# SmartCanBus.net
KiCad netlist of a schematic drawn in Altium Designer
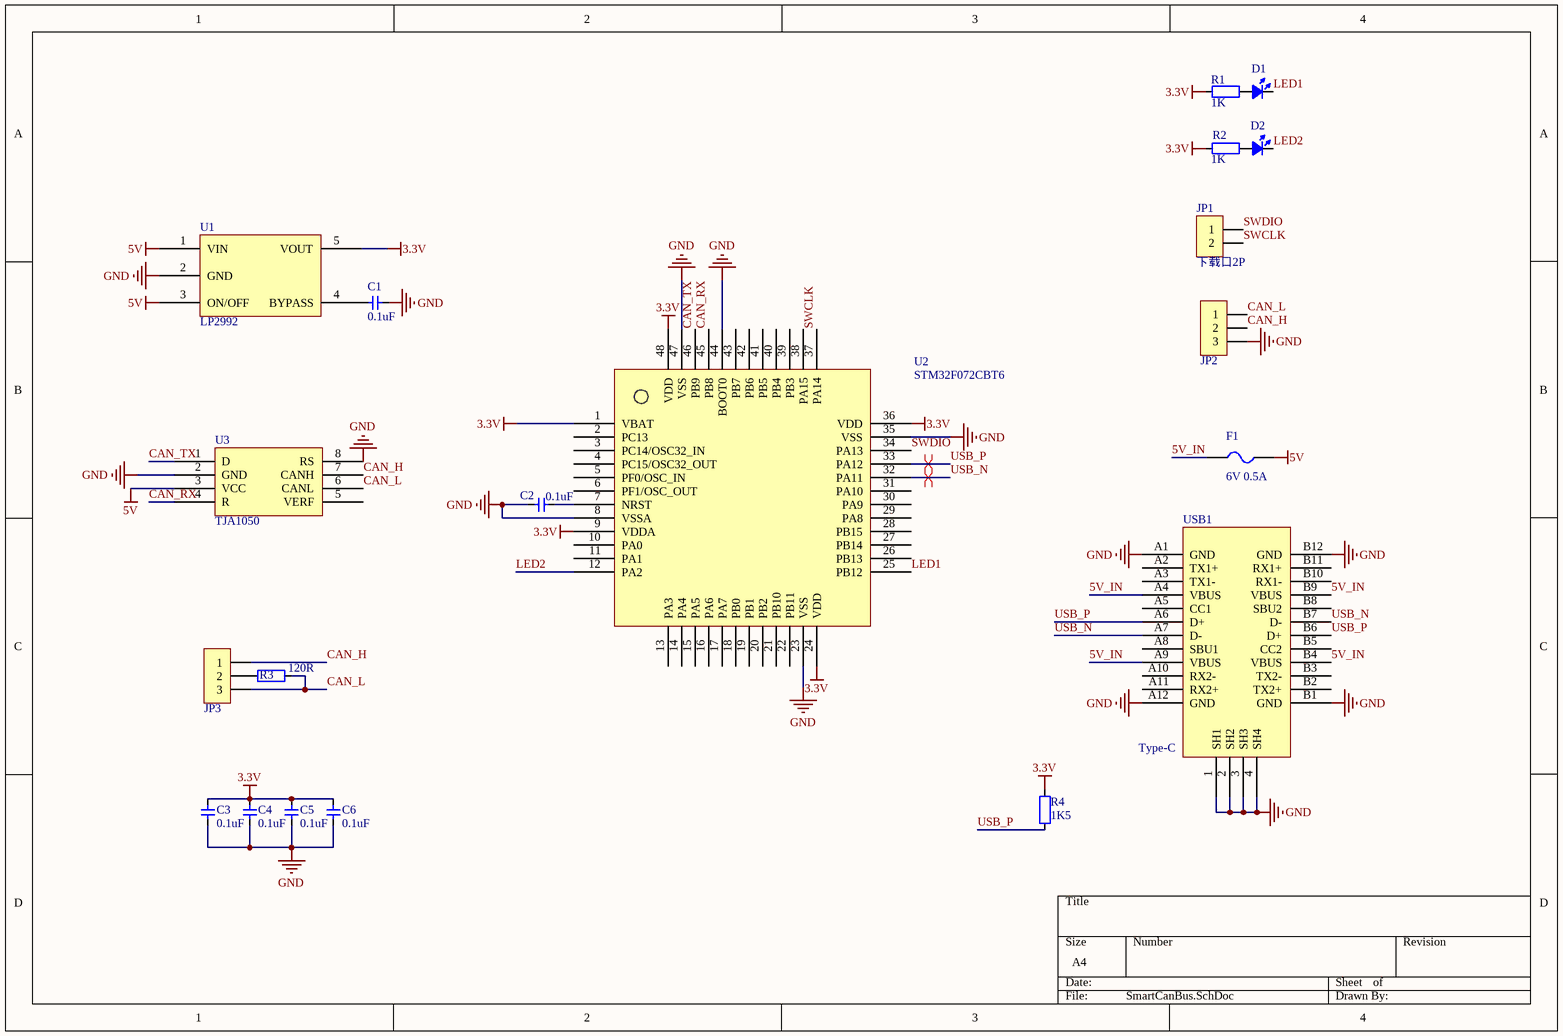
[diagram p0: SmartCanBus.SchDoc]

(export (version "E")
  (design (tool "Eeschema 10.0.6"))
  (components
    (comp (ref "C1")
      (value "0.1uF")
      (footprint "1.00-YltsPcbLib:0603_CAP")
      (description "电容")
      (libsource (lib "0.0 - YltsSchlib") (part "电容-0603"))
    )
    (comp (ref "C2")
      (value "0.1uF")
      (footprint "1.00-YltsPcbLib:0603_CAP")
      (description "电容")
      (libsource (lib "0.0 - YltsSchlib") (part "电容-0603"))
    )
    (comp (ref "C3")
      (value "0.1uF")
      (footprint "1.00-YltsPcbLib:0603_CAP")
      (description "电容")
      (libsource (lib "0.0 - YltsSchlib") (part "电容-0603"))
    )
    (comp (ref "C4")
      (value "0.1uF")
      (footprint "1.00-YltsPcbLib:0603_CAP")
      (description "电容")
      (libsource (lib "0.0 - YltsSchlib") (part "电容-0603"))
    )
    (comp (ref "C5")
      (value "0.1uF")
      (footprint "1.00-YltsPcbLib:0603_CAP")
      (description "电容")
      (libsource (lib "0.0 - YltsSchlib") (part "电容-0603"))
    )
    (comp (ref "C6")
      (value "0.1uF")
      (footprint "1.00-YltsPcbLib:0603_CAP")
      (description "电容")
      (libsource (lib "0.0 - YltsSchlib") (part "电容-0603"))
    )
    (comp (ref "D1")
      (value "LED-0603")
      (footprint "1.00-YltsPcbLib:0603_LED_RED")
      (description "发光二极管")
      (libsource (lib "0.0 - YltsSchlib") (part "二极管-0603-RED"))
    )
    (comp (ref "D2")
      (value "LED-0603")
      (footprint "1.00-YltsPcbLib:0603_LED_BLUE")
      (description "发光二极管")
      (libsource (lib "0.0 - YltsSchlib") (part "二极管-0603-BLUE"))
    )
    (comp (ref "F1")
      (value "6V 0.5A")
      (footprint "FU 0805")
      (description "贴片保险丝")
      (fields (field (name "版权归属") "封装库来自淘宝卖家 ID：黄晶宝石"))
      (libsource (lib "2.0 - 保险丝-晶振-光耦") (part "FU"))
    )
    (comp (ref "JP1")
      (value "下载口2P")
      (footprint "下载口2P")
      (description "下载口2P SWD")
      (libsource (lib "0.0 - YltsSchlib") (part "接插件-下载口2P"))
    )
    (comp (ref "JP2")
      (value "HDR-1X3")
      (footprint "KF128-3.81-3P")
      (description "3P接插件")
      (fields (field (name "版权归属") "封装库来自淘宝 ID：黄晶宝石"))
      (libsource (lib "5.5 - 接插件-脚距3.81 (150mil) ") (part "Header 3"))
    )
    (comp (ref "JP3")
      (value "HDR-1X3")
      (footprint "HDR2.54-LI-3P")
      (description "3P接插件")
      (fields (field (name "版权归属") "封装库来自淘宝 ID：黄晶宝石"))
      (libsource (lib "5.3 - 接插件-脚距2.54 (100mil) ") (part "Header 3"))
    )
    (comp (ref "R1")
      (value "1K")
      (footprint "1.00-YltsPcbLib:0603_RES")
      (description "电阻")
      (libsource (lib "") (part "电阻-0603_1"))
    )
    (comp (ref "R2")
      (value "1K")
      (footprint "1.00-YltsPcbLib:0603_RES")
      (description "电阻")
      (libsource (lib "") (part "电阻-0603_1"))
    )
    (comp (ref "R3")
      (value "120R")
      (footprint "1.00-YltsPcbLib:0603_RES")
      (description "电阻")
      (fields (field (name "Comment") "1K"))
      (libsource (lib "") (part "电阻-0603_1"))
    )
    (comp (ref "R4")
      (value "1K5")
      (footprint "1.00-YltsPcbLib:0603_RES")
      (description "电阻")
      (libsource (lib "0.0 - YltsSchlib") (part "电阻-0603"))
    )
    (comp (ref "U1")
      (value "LP2992")
      (footprint "SOT23-5N")
      (description "电源芯片")
      (libsource (lib "MySchlib") (part "LP2992"))
    )
    (comp (ref "U2")
      (value "STM32F072CBT6")
      (footprint "LQFP-48")
      (description "48MHZ Crotex-M0 32位单片机 LQFP-48_7x7x05P")
      (libsource (lib "0.0 - YltsSchlib") (part "STM32F072CBT6"))
    )
    (comp (ref "U3")
      (value "TJA1050")
      (footprint "SOIC-8 - duplicate")
      (description "CAN芯片")
      (libsource (lib "0.0 - YltsSchlib") (part "TJA1050"))
    )
    (comp (ref "USB1")
      (value "Type-C")
      (footprint "Type-C-TOP")
      (libsource (lib "0.0 - YltsSchlib") (part "接插件-USB-Type-C"))
    )
  )
  (nets
    (net (code "1") (name "/5V_IN") (class "Default")
      (node (ref "F1") (pin "1") (pinfunction "1_1") (pintype "passive"))
      (node (ref "USB1") (pin "A4") (pinfunction "VBUS_A4") (pintype "passive"))
      (node (ref "USB1") (pin "A9") (pinfunction "VBUS_A9") (pintype "passive"))
      (node (ref "USB1") (pin "B4") (pinfunction "VBUS_B4") (pintype "passive"))
      (node (ref "USB1") (pin "B9") (pinfunction "VBUS_B9") (pintype "passive"))
    )
    (net (code "2") (name "/CAN_H") (class "Default")
      (node (ref "JP2") (pin "2") (pinfunction "2_2") (pintype "passive"))
      (node (ref "JP3") (pin "1") (pinfunction "1_1") (pintype "passive"))
      (node (ref "U3") (pin "7") (pinfunction "CANH_7") (pintype "passive"))
    )
    (net (code "3") (name "/CAN_L") (class "Default")
      (node (ref "JP2") (pin "1") (pinfunction "1_1") (pintype "passive"))
      (node (ref "JP3") (pin "3") (pinfunction "3_3") (pintype "passive"))
      (node (ref "R3") (pin "2") (pinfunction "2_2") (pintype "passive"))
      (node (ref "U3") (pin "6") (pinfunction "CANL_6") (pintype "passive"))
    )
    (net (code "4") (name "/CAN_RX") (class "Default")
      (node (ref "U2") (pin "45") (pinfunction "PB8_45") (pintype "passive"))
      (node (ref "U3") (pin "4") (pinfunction "R_4") (pintype "passive"))
    )
    (net (code "5") (name "/CAN_TX") (class "Default")
      (node (ref "U2") (pin "46") (pinfunction "PB9_46") (pintype "passive"))
      (node (ref "U3") (pin "1") (pinfunction "D_1") (pintype "passive"))
    )
    (net (code "6") (name "/LED1") (class "Default")
      (node (ref "D1") (pin "2") (pinfunction "K_2") (pintype "passive"))
      (node (ref "U2") (pin "25") (pinfunction "PB12_25") (pintype "passive"))
    )
    (net (code "7") (name "/LED2") (class "Default")
      (node (ref "D2") (pin "2") (pinfunction "K_2") (pintype "passive"))
      (node (ref "U2") (pin "12") (pinfunction "PA2_12") (pintype "passive"))
    )
    (net (code "8") (name "/SWCLK") (class "Default")
      (node (ref "JP1") (pin "2") (pinfunction "2_2") (pintype "passive"))
      (node (ref "U2") (pin "37") (pinfunction "PA14_37") (pintype "passive"))
    )
    (net (code "9") (name "/SWDIO") (class "Default")
      (node (ref "JP1") (pin "1") (pinfunction "1_1") (pintype "passive"))
      (node (ref "U2") (pin "34") (pinfunction "PA13_34") (pintype "passive"))
    )
    (net (code "10") (name "/USB_N") (class "Default")
      (node (ref "U2") (pin "32") (pinfunction "PA11_32") (pintype "passive"))
      (node (ref "USB1") (pin "A7") (pinfunction "D-_A7") (pintype "passive"))
      (node (ref "USB1") (pin "B7") (pinfunction "D-_B7") (pintype "passive"))
    )
    (net (code "11") (name "/USB_P") (class "Default")
      (node (ref "R4") (pin "1") (pinfunction "1_1") (pintype "passive"))
      (node (ref "U2") (pin "33") (pinfunction "PA12_33") (pintype "passive"))
      (node (ref "USB1") (pin "A6") (pinfunction "D+_A6") (pintype "passive"))
      (node (ref "USB1") (pin "B6") (pinfunction "D+_B6") (pintype "passive"))
    )
    (net (code "12") (name "3.3V") (class "Default")
      (node (ref "C3") (pin "1") (pinfunction "1_1") (pintype "passive"))
      (node (ref "C4") (pin "1") (pinfunction "1_1") (pintype "passive"))
      (node (ref "C5") (pin "1") (pinfunction "1_1") (pintype "passive"))
      (node (ref "C6") (pin "1") (pinfunction "1_1") (pintype "passive"))
      (node (ref "R1") (pin "1") (pinfunction "1_1") (pintype "passive"))
      (node (ref "R2") (pin "1") (pinfunction "1_1") (pintype "passive"))
      (node (ref "R4") (pin "2") (pinfunction "2_2") (pintype "passive"))
      (node (ref "U1") (pin "5") (pinfunction "VOUT_5") (pintype "passive"))
      (node (ref "U2") (pin "1") (pinfunction "VBAT_1") (pintype "passive"))
      (node (ref "U2") (pin "24") (pinfunction "VDD_24") (pintype "passive"))
      (node (ref "U2") (pin "36") (pinfunction "VDD_36") (pintype "passive"))
      (node (ref "U2") (pin "48") (pinfunction "VDD_48") (pintype "passive"))
      (node (ref "U2") (pin "9") (pinfunction "VDDA_9") (pintype "passive"))
    )
    (net (code "13") (name "5V") (class "Default")
      (node (ref "F1") (pin "2") (pinfunction "2_2") (pintype "passive"))
      (node (ref "U1") (pin "1") (pinfunction "VIN_1") (pintype "passive"))
      (node (ref "U1") (pin "3") (pinfunction "ON/OFF_3") (pintype "passive"))
      (node (ref "U3") (pin "3") (pinfunction "VCC_3") (pintype "passive"))
    )
    (net (code "14") (name "GND") (class "Default")
      (node (ref "C1") (pin "1") (pinfunction "1_1") (pintype "passive"))
      (node (ref "C2") (pin "1") (pinfunction "1_1") (pintype "passive"))
      (node (ref "C3") (pin "2") (pinfunction "2_2") (pintype "passive"))
      (node (ref "C4") (pin "2") (pinfunction "2_2") (pintype "passive"))
      (node (ref "C5") (pin "2") (pinfunction "2_2") (pintype "passive"))
      (node (ref "C6") (pin "2") (pinfunction "2_2") (pintype "passive"))
      (node (ref "JP2") (pin "3") (pinfunction "3_3") (pintype "passive"))
      (node (ref "U1") (pin "2") (pinfunction "GND_2") (pintype "passive"))
      (node (ref "U2") (pin "23") (pinfunction "VSS_23") (pintype "passive"))
      (node (ref "U2") (pin "35") (pinfunction "VSS_35") (pintype "passive"))
      (node (ref "U2") (pin "44") (pinfunction "BOOT0_44") (pintype "passive"))
      (node (ref "U2") (pin "47") (pinfunction "VSS_47") (pintype "passive"))
      (node (ref "U2") (pin "8") (pinfunction "VSSA_8") (pintype "passive"))
      (node (ref "U3") (pin "2") (pinfunction "GND_2") (pintype "passive"))
      (node (ref "U3") (pin "8") (pinfunction "RS_8") (pintype "passive"))
      (node (ref "USB1") (pin "1") (pinfunction "SH1_1") (pintype "passive"))
      (node (ref "USB1") (pin "2") (pinfunction "SH2_2") (pintype "passive"))
      (node (ref "USB1") (pin "3") (pinfunction "SH3_3") (pintype "passive"))
      (node (ref "USB1") (pin "4") (pinfunction "SH4_4") (pintype "passive"))
      (node (ref "USB1") (pin "A1") (pinfunction "GND_A1") (pintype "passive"))
      (node (ref "USB1") (pin "A12") (pinfunction "GND_A12") (pintype "passive"))
      (node (ref "USB1") (pin "B1") (pinfunction "GND_B1") (pintype "passive"))
      (node (ref "USB1") (pin "B12") (pinfunction "GND_B12") (pintype "passive"))
    )
    (net (code "15") (name "Net-(D1-A)") (class "Default")
      (node (ref "D1") (pin "1") (pinfunction "A_1") (pintype "passive"))
      (node (ref "R1") (pin "2") (pinfunction "2_2") (pintype "passive"))
    )
    (net (code "16") (name "Net-(D2-A)") (class "Default")
      (node (ref "D2") (pin "1") (pinfunction "A_1") (pintype "passive"))
      (node (ref "R2") (pin "2") (pinfunction "2_2") (pintype "passive"))
    )
    (net (code "17") (name "Net-(JP3-Pad2)") (class "Default")
      (node (ref "JP3") (pin "2") (pinfunction "2_2") (pintype "passive"))
      (node (ref "R3") (pin "1") (pinfunction "1_1") (pintype "passive"))
    )
    (net (code "18") (name "Net-(U1-BYPASS)") (class "Default")
      (node (ref "C1") (pin "2") (pinfunction "2_2") (pintype "passive"))
      (node (ref "U1") (pin "4") (pinfunction "BYPASS_4") (pintype "passive"))
    )
    (net (code "19") (name "Net-(U2-NRST)") (class "Default")
      (node (ref "C2") (pin "2") (pinfunction "2_2") (pintype "passive"))
      (node (ref "U2") (pin "7") (pinfunction "NRST_7") (pintype "passive"))
    )
    (net (code "20") (name "unconnected-(U2-PA0-Pad10)") (class "Default")
      (node (ref "U2") (pin "10") (pinfunction "PA0_10") (pintype "passive"))
    )
    (net (code "21") (name "unconnected-(U2-PA1-Pad11)") (class "Default")
      (node (ref "U2") (pin "11") (pinfunction "PA1_11") (pintype "passive"))
    )
    (net (code "22") (name "unconnected-(U2-PA3-Pad13)") (class "Default")
      (node (ref "U2") (pin "13") (pinfunction "PA3_13") (pintype "passive"))
    )
    (net (code "23") (name "unconnected-(U2-PA4-Pad14)") (class "Default")
      (node (ref "U2") (pin "14") (pinfunction "PA4_14") (pintype "passive"))
    )
    (net (code "24") (name "unconnected-(U2-PA5-Pad15)") (class "Default")
      (node (ref "U2") (pin "15") (pinfunction "PA5_15") (pintype "passive"))
    )
    (net (code "25") (name "unconnected-(U2-PA6-Pad16)") (class "Default")
      (node (ref "U2") (pin "16") (pinfunction "PA6_16") (pintype "passive"))
    )
    (net (code "26") (name "unconnected-(U2-PA7-Pad17)") (class "Default")
      (node (ref "U2") (pin "17") (pinfunction "PA7_17") (pintype "passive"))
    )
    (net (code "27") (name "unconnected-(U2-PA8-Pad29)") (class "Default")
      (node (ref "U2") (pin "29") (pinfunction "PA8_29") (pintype "passive"))
    )
    (net (code "28") (name "unconnected-(U2-PA9-Pad30)") (class "Default")
      (node (ref "U2") (pin "30") (pinfunction "PA9_30") (pintype "passive"))
    )
    (net (code "29") (name "unconnected-(U2-PA10-Pad31)") (class "Default")
      (node (ref "U2") (pin "31") (pinfunction "PA10_31") (pintype "passive"))
    )
    (net (code "30") (name "unconnected-(U2-PA15-Pad38)") (class "Default")
      (node (ref "U2") (pin "38") (pinfunction "PA15_38") (pintype "passive"))
    )
    (net (code "31") (name "unconnected-(U2-PB0-Pad18)") (class "Default")
      (node (ref "U2") (pin "18") (pinfunction "PB0_18") (pintype "passive"))
    )
    (net (code "32") (name "unconnected-(U2-PB1-Pad19)") (class "Default")
      (node (ref "U2") (pin "19") (pinfunction "PB1_19") (pintype "passive"))
    )
    (net (code "33") (name "unconnected-(U2-PB2-Pad20)") (class "Default")
      (node (ref "U2") (pin "20") (pinfunction "PB2_20") (pintype "passive"))
    )
    (net (code "34") (name "unconnected-(U2-PB3-Pad39)") (class "Default")
      (node (ref "U2") (pin "39") (pinfunction "PB3_39") (pintype "passive"))
    )
    (net (code "35") (name "unconnected-(U2-PB4-Pad40)") (class "Default")
      (node (ref "U2") (pin "40") (pinfunction "PB4_40") (pintype "passive"))
    )
    (net (code "36") (name "unconnected-(U2-PB5-Pad41)") (class "Default")
      (node (ref "U2") (pin "41") (pinfunction "PB5_41") (pintype "passive"))
    )
    (net (code "37") (name "unconnected-(U2-PB6-Pad42)") (class "Default")
      (node (ref "U2") (pin "42") (pinfunction "PB6_42") (pintype "passive"))
    )
    (net (code "38") (name "unconnected-(U2-PB7-Pad43)") (class "Default")
      (node (ref "U2") (pin "43") (pinfunction "PB7_43") (pintype "passive"))
    )
    (net (code "39") (name "unconnected-(U2-PB10-Pad21)") (class "Default")
      (node (ref "U2") (pin "21") (pinfunction "PB10_21") (pintype "passive"))
    )
    (net (code "40") (name "unconnected-(U2-PB11-Pad22)") (class "Default")
      (node (ref "U2") (pin "22") (pinfunction "PB11_22") (pintype "passive"))
    )
    (net (code "41") (name "unconnected-(U2-PB13-Pad26)") (class "Default")
      (node (ref "U2") (pin "26") (pinfunction "PB13_26") (pintype "passive"))
    )
    (net (code "42") (name "unconnected-(U2-PB14-Pad27)") (class "Default")
      (node (ref "U2") (pin "27") (pinfunction "PB14_27") (pintype "passive"))
    )
    (net (code "43") (name "unconnected-(U2-PB15-Pad28)") (class "Default")
      (node (ref "U2") (pin "28") (pinfunction "PB15_28") (pintype "passive"))
    )
    (net (code "44") (name "unconnected-(U2-PC13-Pad2)") (class "Default")
      (node (ref "U2") (pin "2") (pinfunction "PC13_2") (pintype "passive"))
    )
    (net (code "45") (name "unconnected-(U2-PC14{slash}OSC32_IN-Pad3)") (class "Default")
      (node (ref "U2") (pin "3") (pinfunction "PC14/OSC32_IN_3") (pintype "passive"))
    )
    (net (code "46") (name "unconnected-(U2-PC15{slash}OSC32_OUT-Pad4)") (class "Default")
      (node (ref "U2") (pin "4") (pinfunction "PC15/OSC32_OUT_4") (pintype "passive"))
    )
    (net (code "47") (name "unconnected-(U2-PF0{slash}OSC_IN-Pad5)") (class "Default")
      (node (ref "U2") (pin "5") (pinfunction "PF0/OSC_IN_5") (pintype "passive"))
    )
    (net (code "48") (name "unconnected-(U2-PF1{slash}OSC_OUT-Pad6)") (class "Default")
      (node (ref "U2") (pin "6") (pinfunction "PF1/OSC_OUT_6") (pintype "passive"))
    )
    (net (code "49") (name "unconnected-(U3-VERF-Pad5)") (class "Default")
      (node (ref "U3") (pin "5") (pinfunction "VERF_5") (pintype "passive"))
    )
    (net (code "50") (name "unconnected-(USB1-CC1-PadA5)") (class "Default")
      (node (ref "USB1") (pin "A5") (pinfunction "CC1_A5") (pintype "passive"))
    )
    (net (code "51") (name "unconnected-(USB1-CC2-PadB5)") (class "Default")
      (node (ref "USB1") (pin "B5") (pinfunction "CC2_B5") (pintype "passive"))
    )
    (net (code "52") (name "unconnected-(USB1-RX1+-PadB11)") (class "Default")
      (node (ref "USB1") (pin "B11") (pinfunction "RX1+_B11") (pintype "passive"))
    )
    (net (code "53") (name "unconnected-(USB1-RX1--PadB10)") (class "Default")
      (node (ref "USB1") (pin "B10") (pinfunction "RX1-_B10") (pintype "passive"))
    )
    (net (code "54") (name "unconnected-(USB1-RX2+-PadA11)") (class "Default")
      (node (ref "USB1") (pin "A11") (pinfunction "RX2+_A11") (pintype "passive"))
    )
    (net (code "55") (name "unconnected-(USB1-RX2--PadA10)") (class "Default")
      (node (ref "USB1") (pin "A10") (pinfunction "RX2-_A10") (pintype "passive"))
    )
    (net (code "56") (name "unconnected-(USB1-SBU1-PadA8)") (class "Default")
      (node (ref "USB1") (pin "A8") (pinfunction "SBU1_A8") (pintype "passive"))
    )
    (net (code "57") (name "unconnected-(USB1-SBU2-PadB8)") (class "Default")
      (node (ref "USB1") (pin "B8") (pinfunction "SBU2_B8") (pintype "passive"))
    )
    (net (code "58") (name "unconnected-(USB1-TX1+-PadA2)") (class "Default")
      (node (ref "USB1") (pin "A2") (pinfunction "TX1+_A2") (pintype "passive"))
    )
    (net (code "59") (name "unconnected-(USB1-TX1--PadA3)") (class "Default")
      (node (ref "USB1") (pin "A3") (pinfunction "TX1-_A3") (pintype "passive"))
    )
    (net (code "60") (name "unconnected-(USB1-TX2+-PadB2)") (class "Default")
      (node (ref "USB1") (pin "B2") (pinfunction "TX2+_B2") (pintype "passive"))
    )
    (net (code "61") (name "unconnected-(USB1-TX2--PadB3)") (class "Default")
      (node (ref "USB1") (pin "B3") (pinfunction "TX2-_B3") (pintype "passive"))
    )
  )
)
